# BuckRegulatorOnSer.net
KiCad netlist of a schematic drawn in Altium Designer
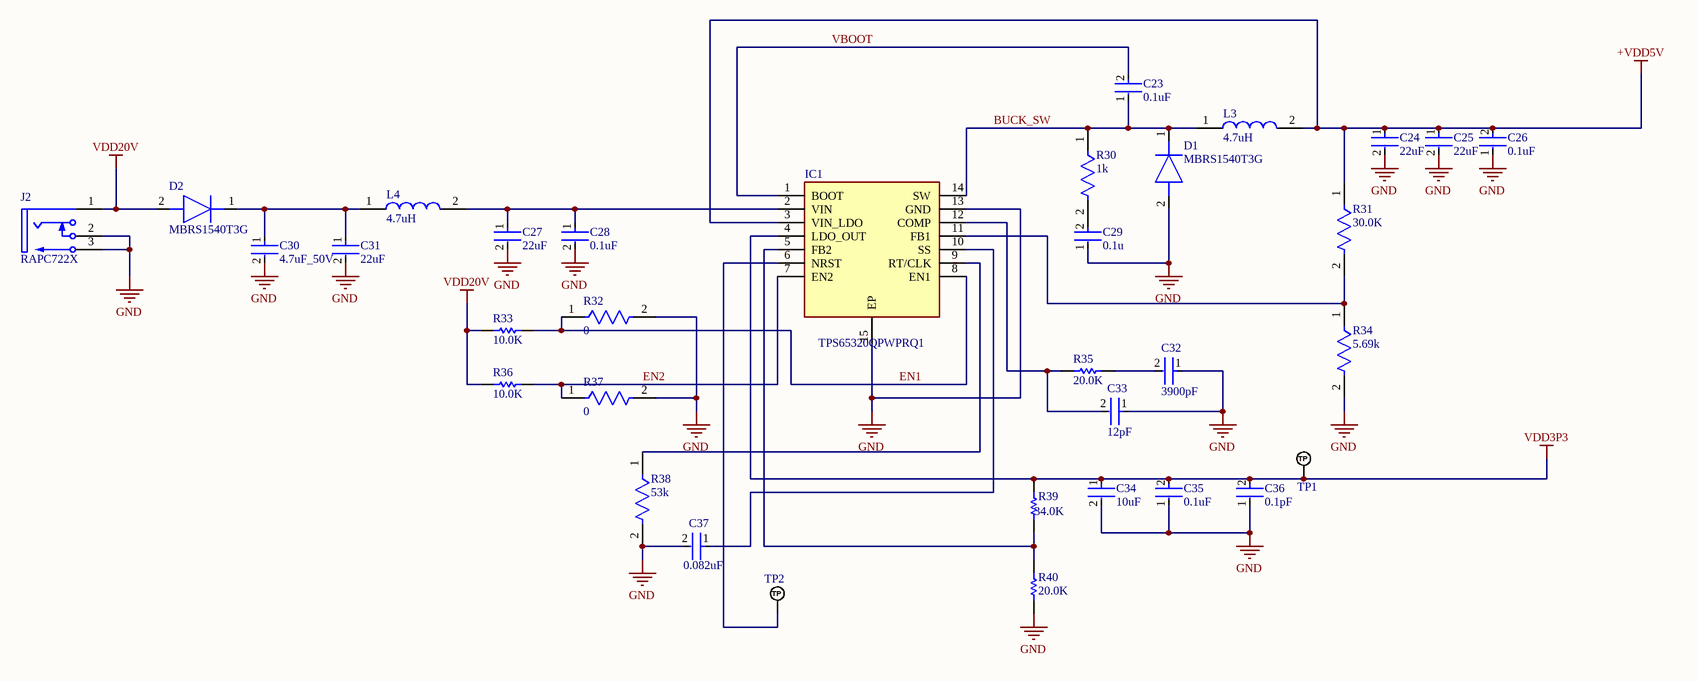
[diagram p0: BuckRegulatorOnSer.SchDoc]

(export (version "E")
  (design (tool "Eeschema 10.0.6"))
  (components
    (comp (ref "C23")
      (value "0.1uF")
      (footprint "FP-GRM15-MFG")
      (description "CAP CER 0.1UF 16V X7R 0402")
      (fields (field (name "MANUFACTURER PART NUMBER") "GRM155R71C104KA88D") (field (name "TOLERANCE") "10%"))
      (libsource (lib "Altium Content Vault") (part "236180d848d6139a670b325ea6854c9"))
    )
    (comp (ref "C24")
      (value "22uF")
      (footprint "FP-C3216-160-0_2-IPC_B")
      (description "Multilayer Ceramic Capacitors 22uF ±20% 25V X5R SMD 1206")
      (fields (field (name "TOLERANCE") "20%"))
      (libsource (lib "Altium Content Vault") (part "11868f565c42a9108669ba33697ecf6"))
    )
    (comp (ref "C25")
      (value "22uF")
      (footprint "FP-C3216-160-0_2-IPC_B")
      (description "Multilayer Ceramic Capacitors 22uF ±20% 25V X5R SMD 1206")
      (fields (field (name "TOLERANCE") "20%"))
      (libsource (lib "Altium Content Vault") (part "11868f565c42a9108669ba33697ecf6"))
    )
    (comp (ref "C26")
      (value "0.1uF")
      (footprint "FP-GRM15-MFG")
      (description "CAP CER 0.1UF 16V X7R 0402")
      (fields (field (name "MANUFACTURER PART NUMBER") "GRM155R71C104KA88D") (field (name "TOLERANCE") "10%"))
      (libsource (lib "Altium Content Vault") (part "236180d848d6139a670b325ea6854c9"))
    )
    (comp (ref "C27")
      (value "22uF")
      (footprint "FP-C3216-160-0_2-IPC_B")
      (description "Multilayer Ceramic Capacitors 22uF ±20% 25V X5R SMD 1206")
      (fields (field (name "TOLERANCE") "20%"))
      (libsource (lib "Altium Content Vault") (part "11868f565c42a9108669ba33697ecf6"))
    )
    (comp (ref "C28")
      (value "0.1uF")
      (footprint "FP-GRM188-0_1-e0_2_0_5-IPC_B")
      (description "Chip Multilayer Ceramic Capacitors for General Purpose, 0603, 0.10uF, X7R, 15%, 10%, 100V")
      (fields (field (name "VOLTAGE") "100V") (field (name "TOLERANCE") "10%"))
      (libsource (lib "Altium Content Vault") (part "11868f565c42a9108669ba33697ecf6"))
    )
    (comp (ref "C29")
      (value "0.1u")
      (footprint "FP-GRM15-MFG")
      (description "CAP CER 0.1UF 16V X7R 0402")
      (fields (field (name "MANUFACTURER PART NUMBER") "GRM155R71C104KA88D") (field (name "TOLERANCE") "10%"))
      (libsource (lib "Altium Content Vault") (part "236180d848d6139a670b325ea6854c9"))
    )
    (comp (ref "C30")
      (value "4.7uF_50V")
      (footprint "FP-C3216-160-0_2-IPC_B")
      (description "Multilayer Ceramic Capacitors 4.7uF ±20% 50V X7R SMD 1206")
      (fields (field (name "TOLERANCE") "20%"))
      (libsource (lib "Altium Content Vault") (part "11868f565c42a9108669ba33697ecf6"))
    )
    (comp (ref "C31")
      (value "22uF")
      (footprint "FP-C3216-160-0_2-IPC_B")
      (description "Multilayer Ceramic Capacitors 22uF ±20% 25V X5R SMD 1206")
      (fields (field (name "TOLERANCE") "20%"))
      (libsource (lib "Altium Content Vault") (part "11868f565c42a9108669ba33697ecf6"))
    )
    (comp (ref "C32")
      (value "3900pF")
      (footprint "FP-C0402-BB-MFG")
      (description "CAP CER 3900PF 16V X7R 0402")
      (fields
        (field (name "MANUFACTURER PART NUMBER") "C0402C392K4RACTU")
        (field (name "OCTOPART") "https://octopart.com/c0402c392k4ractu-kemet-12577363")
      )
      (libsource (lib "Altium Content Vault") (part "b4654b650e69147ec39a6b967a45e02"))
    )
    (comp (ref "C33")
      (value "12pF")
      (footprint "FP-C0402-BB-MFG")
      (description "CAP CER 12PF 25V C0G/NP0 0402")
      (fields
        (field (name "OCTOPART") "https://octopart.com/c0402c120j3gacauto-kemet-21768529")
        (field (name "MANUFACTURER PART NUMBER") "C0402C120J3GACAUTO")
      )
      (libsource (lib "Altium Content Vault") (part "b4654b650e69147ec39a6b967a45e02"))
    )
    (comp (ref "C34")
      (value "10uF")
      (footprint "FP-C2012-125-0_2-MFG")
      (description "Multilayer Ceramic Capacitors 10μF ±10% 10V X7R SMD 0805")
      (fields (field (name "TOLERANCE") "10%") (field (name "VOLTAGE") "10V"))
      (libsource (lib "Altium Content Vault") (part "b4654b650e69147ec39a6b967a45e02"))
    )
    (comp (ref "C35")
      (value "0.1uF")
      (footprint "FP-GRM15-MFG")
      (description "CAP CER 0.1UF 16V X7R 0402")
      (fields (field (name "MANUFACTURER PART NUMBER") "GRM155R71C104KA88D") (field (name "TOLERANCE") "10%"))
      (libsource (lib "Altium Content Vault") (part "236180d848d6139a670b325ea6854c9"))
    )
    (comp (ref "C36")
      (value "0.1pF")
      (footprint "FP-GRM15-MFG")
      (description "CAP CER 0.1UF 16V X7R 0402")
      (fields (field (name "MANUFACTURER PART NUMBER") "GRM155R71C104KA88D") (field (name "TOLERANCE") "10%"))
      (libsource (lib "Altium Content Vault") (part "236180d848d6139a670b325ea6854c9"))
    )
    (comp (ref "C37")
      (value "0.082uF")
      (footprint "FP-C0402-BB-MFG")
      (fields
        (field (name "OCTOPART") "https://octopart.com/c0402c823k4ractu-kemet-134782")
        (field (name "MANUFACTURER") "Kemet")
        (field (name "TOLERANCE") "0.1")
      )
      (libsource (lib "Altium Content Vault") (part "b4654b650e69147ec39a6b967a45e02"))
    )
    (comp (ref "D1")
      (value "MBRS1540T3G")
      (footprint "SerDes_Eval_Board_Footprints:DIOM5436X256N")
      (description "Diode")
      (fields (field (name "MOUSER PART NUMBER") "863-MBRS1540T3G"))
      (libsource (lib "SerDes_Eval") (part "MBRS1540T3G"))
    )
    (comp (ref "D2")
      (value "MBRS1540T3G")
      (footprint "SerDes_Eval_Board_Footprints:DIOM5436X256N")
      (description "Diode")
      (fields (field (name "MOUSER PART NUMBER") "863-MBRS1540T3G"))
      (libsource (lib "SerDes_Eval") (part "MBRS1540T3G"))
    )
    (comp (ref "IC1")
      (value "TPS65320QPWPRQ1")
      (footprint "SerDes_Eval_Board_Footprints:SOP65P640X120-15N")
      (description "Integrated Circuit")
      (fields (field (name "MOUSER PART NUMBER") "595-TPS65320QPWPRQ1"))
      (libsource (lib "SerDes_Eval") (part "TPS65320QPWPRQ1"))
    )
    (comp (ref "J2")
      (value "RAPC722X")
      (footprint "SWITCH-RAPC712X-3_V")
      (description "Power Jack, 5 A, 3-Pin THD, RoHS, Bulk")
      (fields (field (name "MANUFACTURER") "Switchcraft"))
      (libsource (lib "Altium Content Vault") (part "SWITCH-RAPC712X-3"))
    )
    (comp (ref "L3")
      (value "4.7uH")
      (footprint "SerDes_Eval_Board_Footprints:XFL4020472MEB")
      (description "Inductor")
      (fields
        (field (name "MANUFACTURER_PART_NUMBER") "XFL4020-472MEB")
        (field (name "MOUSER PART NUMBER") "994-XFL4020-472MEB")
      )
      (libsource (lib "SerDes_Eval") (part "XFL4020-472MEB"))
    )
    (comp (ref "L4")
      (value "4.7uH")
      (footprint "SerDes_Eval_Board_Footprints:XFL4020472MEB")
      (description "Inductor")
      (fields
        (field (name "MANUFACTURER_PART_NUMBER") "XFL4020-472MEB")
        (field (name "MOUSER PART NUMBER") "994-XFL4020-472MEB")
      )
      (libsource (lib "SerDes_Eval") (part "XFL4020-472MEB"))
    )
    (comp (ref "R30")
      (value "1k")
      (footprint "FP-CRCW0603-e3-MFG")
      (description "RES Thick Film, 1kΩ, 1%, 0.1W, 100ppm/°C, 0603")
      (fields (field (name "TOLERANCE") "1%"))
      (libsource (lib "Altium Content Vault") (part "1029c3af85768c4190bb7ad29bc67b5"))
    )
    (comp (ref "R31")
      (value "30.0K")
      (footprint "FP-ERJ3EK-IPC_A")
      (description "RES SMD 30K OHM 1% 1/10W 0603")
      (fields (field (name "TOLERANCE") "1%"))
      (libsource (lib "Altium Content Vault") (part "1029c3af85768c4190bb7ad29bc67b5"))
    )
    (comp (ref "R32")
      (value "0")
      (footprint "FP-ERJ-3GEY0R00V-MFG")
      (description "RES SMD 0 OHM JUMPER 1/10W 0603")
      (fields (field (name "TOLERANCE") "5%") (field (name "MANUFACTURER PART NUMBER") "ERJ-3GEY0R00V"))
      (libsource (lib "Altium Content Vault") (part "1029c3af85768c4190bb7ad29bc67b5"))
    )
    (comp (ref "R33")
      (value "10.0K")
      (footprint "RESC1609X55X30LL15T15")
      (description "Chip Resistor, 10 KOhm, +/- 1%, 0.1 W, -55 to 155 degC, 0603 (1608 Metric), RoHS, Tape and Reel")
      (fields (field (name "TOLERANCE") "1%") (field (name "MANUFACTURER") "Panasonic"))
      (libsource (lib "Altium Content Vault") (part "RES-2"))
    )
    (comp (ref "R34")
      (value "5.69k")
      (footprint "FP-RN73R1E-IPC_A")
      (description "5.69kΩ ±0.1% 0.063W, 1/16W Chip Resistor 0402 (1005 Metric) Moisture Resistant Thin Film")
      (libsource (lib "Altium Content Vault") (part "1029c3af85768c4190bb7ad29bc67b5"))
    )
    (comp (ref "R35")
      (value "20.0K")
      (footprint "RESC1608X55X30ML15T15")
      (fields (field (name "PART NUMBER") "ERJ-3EKF2002V") (field (name "MANUFACTURER") "Panasonic"))
      (libsource (lib "Altium Content Vault") (part "RES"))
    )
    (comp (ref "R36")
      (value "10.0K")
      (footprint "RESC1609X55X30LL15T15")
      (description "Chip Resistor, 10 KOhm, +/- 1%, 0.1 W, -55 to 155 degC, 0603 (1608 Metric), RoHS, Tape and Reel")
      (fields (field (name "TOLERANCE") "1%") (field (name "MANUFACTURER") "Panasonic"))
      (libsource (lib "Altium Content Vault") (part "RES-2"))
    )
    (comp (ref "R37")
      (value "0")
      (footprint "FP-ERJ-3GEY0R00V-MFG")
      (description "RES SMD 0 OHM JUMPER 1/10W 0603")
      (fields (field (name "TOLERANCE") "5%") (field (name "MANUFACTURER PART NUMBER") "ERJ-3GEY0R00V"))
      (libsource (lib "Altium Content Vault") (part "1029c3af85768c4190bb7ad29bc67b5"))
    )
    (comp (ref "R38")
      (value "53k")
      (footprint "FP-RN73R1E-MFG")
      (description "53kΩ ±0.1% 0.063W, 1/16W Chip Resistor 0402 (1005 Metric) Moisture Resistant Thin Film")
      (libsource (lib "Altium Content Vault") (part "1029c3af85768c4190bb7ad29bc67b5"))
    )
    (comp (ref "R39")
      (value "34.0K")
      (footprint "RESC1608X55X30ML15T15")
      (fields (field (name "PART NUMBER") "ERJ-3EKF3402V") (field (name "MANUFACTURER") "Panasonic"))
      (libsource (lib "Altium Content Vault") (part "RES"))
    )
    (comp (ref "R40")
      (value "20.0K")
      (footprint "RESC1608X55X30ML15T15")
      (fields (field (name "PART NUMBER") "ERJ-3EKF2002V") (field (name "MANUFACTURER") "Panasonic"))
      (libsource (lib "Altium Content Vault") (part "RES"))
    )
    (comp (ref "TP1")
      (value "TP_NOBOM")
      (footprint "PAD_RND_1MM")
      (description "Test Point Round 1mm (NO BOM)")
      (libsource (lib "Custom_Schematic-Lib") (part "TEST_POINT_RND_1MM"))
    )
    (comp (ref "TP2")
      (value "TP_NOBOM")
      (footprint "PAD_RND_1MM")
      (description "Test Point Round 1mm (NO BOM)")
      (libsource (lib "Custom_Schematic-Lib") (part "TEST_POINT_RND_1MM"))
    )
  )
  (nets
    (net (code "1") (name "+VDD5V") (class "Default")
      (node (ref "C24") (pin "1") (pinfunction "1_1") (pintype "passive"))
      (node (ref "C25") (pin "1") (pinfunction "1_1") (pintype "passive"))
      (node (ref "C26") (pin "2") (pinfunction "2_2") (pintype "passive"))
      (node (ref "IC1") (pin "3") (pinfunction "VIN_LDO_3") (pintype "passive"))
      (node (ref "L3") (pin "2") (pinfunction "2_2") (pintype "passive"))
      (node (ref "R31") (pin "1") (pinfunction "1_1") (pintype "passive"))
    )
    (net (code "2") (name "/BUCK_SW") (class "Default")
      (node (ref "C23") (pin "1") (pinfunction "1_1") (pintype "passive"))
      (node (ref "D1") (pin "1") (pinfunction "K_1") (pintype "passive"))
      (node (ref "IC1") (pin "14") (pinfunction "SW_14") (pintype "passive"))
      (node (ref "L3") (pin "1") (pinfunction "1_1") (pintype "passive"))
      (node (ref "R30") (pin "1") (pinfunction "1_1") (pintype "passive"))
    )
    (net (code "3") (name "/EN1") (class "Default")
      (node (ref "IC1") (pin "8") (pinfunction "EN1_8") (pintype "passive"))
      (node (ref "R32") (pin "1") (pinfunction "1_1") (pintype "passive"))
      (node (ref "R33") (pin "2") (pinfunction "2_2") (pintype "passive"))
    )
    (net (code "4") (name "/EN2") (class "Default")
      (node (ref "IC1") (pin "7") (pinfunction "EN2_7") (pintype "passive"))
      (node (ref "R36") (pin "2") (pinfunction "2_2") (pintype "passive"))
      (node (ref "R37") (pin "1") (pinfunction "1_1") (pintype "passive"))
    )
    (net (code "5") (name "/VBOOT") (class "Default")
      (node (ref "C23") (pin "2") (pinfunction "2_2") (pintype "passive"))
      (node (ref "IC1") (pin "1") (pinfunction "BOOT_1") (pintype "passive"))
    )
    (net (code "6") (name "GND") (class "Default")
      (node (ref "C24") (pin "2") (pinfunction "2_2") (pintype "passive"))
      (node (ref "C25") (pin "2") (pinfunction "2_2") (pintype "passive"))
      (node (ref "C26") (pin "1") (pinfunction "1_1") (pintype "passive"))
      (node (ref "C27") (pin "2") (pinfunction "2_2") (pintype "passive"))
      (node (ref "C28") (pin "2") (pinfunction "2_2") (pintype "passive"))
      (node (ref "C29") (pin "1") (pinfunction "1_1") (pintype "passive"))
      (node (ref "C30") (pin "2") (pinfunction "2_2") (pintype "passive"))
      (node (ref "C31") (pin "2") (pinfunction "2_2") (pintype "passive"))
      (node (ref "C32") (pin "1") (pinfunction "1_1") (pintype "passive"))
      (node (ref "C33") (pin "1") (pinfunction "1_1") (pintype "passive"))
      (node (ref "C34") (pin "2") (pinfunction "2_2") (pintype "passive"))
      (node (ref "C35") (pin "1") (pinfunction "1_1") (pintype "passive"))
      (node (ref "C36") (pin "1") (pinfunction "1_1") (pintype "passive"))
      (node (ref "C37") (pin "2") (pinfunction "2_2") (pintype "passive"))
      (node (ref "D1") (pin "2") (pinfunction "A_2") (pintype "passive"))
      (node (ref "IC1") (pin "13") (pinfunction "GND_13") (pintype "passive"))
      (node (ref "IC1") (pin "15") (pinfunction "EP_15") (pintype "passive"))
      (node (ref "J2") (pin "2") (pinfunction "2_2") (pintype "passive"))
      (node (ref "J2") (pin "3") (pinfunction "3_3") (pintype "passive"))
      (node (ref "R32") (pin "2") (pinfunction "2_2") (pintype "passive"))
      (node (ref "R34") (pin "2") (pinfunction "2_2") (pintype "passive"))
      (node (ref "R37") (pin "2") (pinfunction "2_2") (pintype "passive"))
      (node (ref "R38") (pin "2") (pinfunction "2_2") (pintype "passive"))
      (node (ref "R40") (pin "2") (pinfunction "2_2") (pintype "passive"))
    )
    (net (code "7") (name "Net-(C29-Pad2)") (class "Default")
      (node (ref "C29") (pin "2") (pinfunction "2_2") (pintype "passive"))
      (node (ref "R30") (pin "2") (pinfunction "2_2") (pintype "passive"))
    )
    (net (code "8") (name "Net-(C32-Pad2)") (class "Default")
      (node (ref "C32") (pin "2") (pinfunction "2_2") (pintype "passive"))
      (node (ref "R35") (pin "2") (pinfunction "2_2") (pintype "passive"))
    )
    (net (code "9") (name "Net-(D2-K)") (class "Default")
      (node (ref "C30") (pin "1") (pinfunction "1_1") (pintype "passive"))
      (node (ref "C31") (pin "1") (pinfunction "1_1") (pintype "passive"))
      (node (ref "D2") (pin "1") (pinfunction "K_1") (pintype "passive"))
      (node (ref "L4") (pin "1") (pinfunction "1_1") (pintype "passive"))
    )
    (net (code "10") (name "Net-(IC1-COMP)") (class "Default")
      (node (ref "C33") (pin "2") (pinfunction "2_2") (pintype "passive"))
      (node (ref "IC1") (pin "12") (pinfunction "COMP_12") (pintype "passive"))
      (node (ref "R35") (pin "1") (pinfunction "1_1") (pintype "passive"))
    )
    (net (code "11") (name "Net-(IC1-FB1)") (class "Default")
      (node (ref "IC1") (pin "11") (pinfunction "FB1_11") (pintype "passive"))
      (node (ref "R31") (pin "2") (pinfunction "2_2") (pintype "passive"))
      (node (ref "R34") (pin "1") (pinfunction "1_1") (pintype "passive"))
    )
    (net (code "12") (name "Net-(IC1-FB2)") (class "Default")
      (node (ref "IC1") (pin "5") (pinfunction "FB2_5") (pintype "passive"))
      (node (ref "R39") (pin "2") (pinfunction "2_2") (pintype "passive"))
      (node (ref "R40") (pin "1") (pinfunction "1_1") (pintype "passive"))
    )
    (net (code "13") (name "Net-(IC1-NRST)") (class "Default")
      (node (ref "IC1") (pin "6") (pinfunction "NRST_6") (pintype "passive"))
      (node (ref "TP2") (pin "1") (pinfunction "TP_1") (pintype "passive"))
    )
    (net (code "14") (name "Net-(IC1-RT{slash}CLK)") (class "Default")
      (node (ref "IC1") (pin "9") (pinfunction "RT/CLK_9") (pintype "passive"))
      (node (ref "R38") (pin "1") (pinfunction "1_1") (pintype "passive"))
    )
    (net (code "15") (name "Net-(IC1-SS)") (class "Default")
      (node (ref "C37") (pin "1") (pinfunction "1_1") (pintype "passive"))
      (node (ref "IC1") (pin "10") (pinfunction "SS_10") (pintype "passive"))
    )
    (net (code "16") (name "Net-(IC1-VIN)") (class "Default")
      (node (ref "C27") (pin "1") (pinfunction "1_1") (pintype "passive"))
      (node (ref "C28") (pin "1") (pinfunction "1_1") (pintype "passive"))
      (node (ref "IC1") (pin "2") (pinfunction "VIN_2") (pintype "passive"))
      (node (ref "L4") (pin "2") (pinfunction "2_2") (pintype "passive"))
    )
    (net (code "17") (name "VDD3P3") (class "Default")
      (node (ref "C34") (pin "1") (pinfunction "1_1") (pintype "passive"))
      (node (ref "C35") (pin "2") (pinfunction "2_2") (pintype "passive"))
      (node (ref "C36") (pin "2") (pinfunction "2_2") (pintype "passive"))
      (node (ref "IC1") (pin "4") (pinfunction "LDO_OUT_4") (pintype "passive"))
      (node (ref "R39") (pin "1") (pinfunction "1_1") (pintype "passive"))
      (node (ref "TP1") (pin "1") (pinfunction "TP_1") (pintype "passive"))
    )
    (net (code "18") (name "VDD20V") (class "Default")
      (node (ref "D2") (pin "2") (pinfunction "A_2") (pintype "passive"))
      (node (ref "J2") (pin "1") (pinfunction "1_1") (pintype "passive"))
      (node (ref "R33") (pin "1") (pinfunction "1_1") (pintype "passive"))
      (node (ref "R36") (pin "1") (pinfunction "1_1") (pintype "passive"))
    )
  )
)
